# d150_zm1000_rev_a.net
KiCad netlist of a schematic drawn in EAGLE
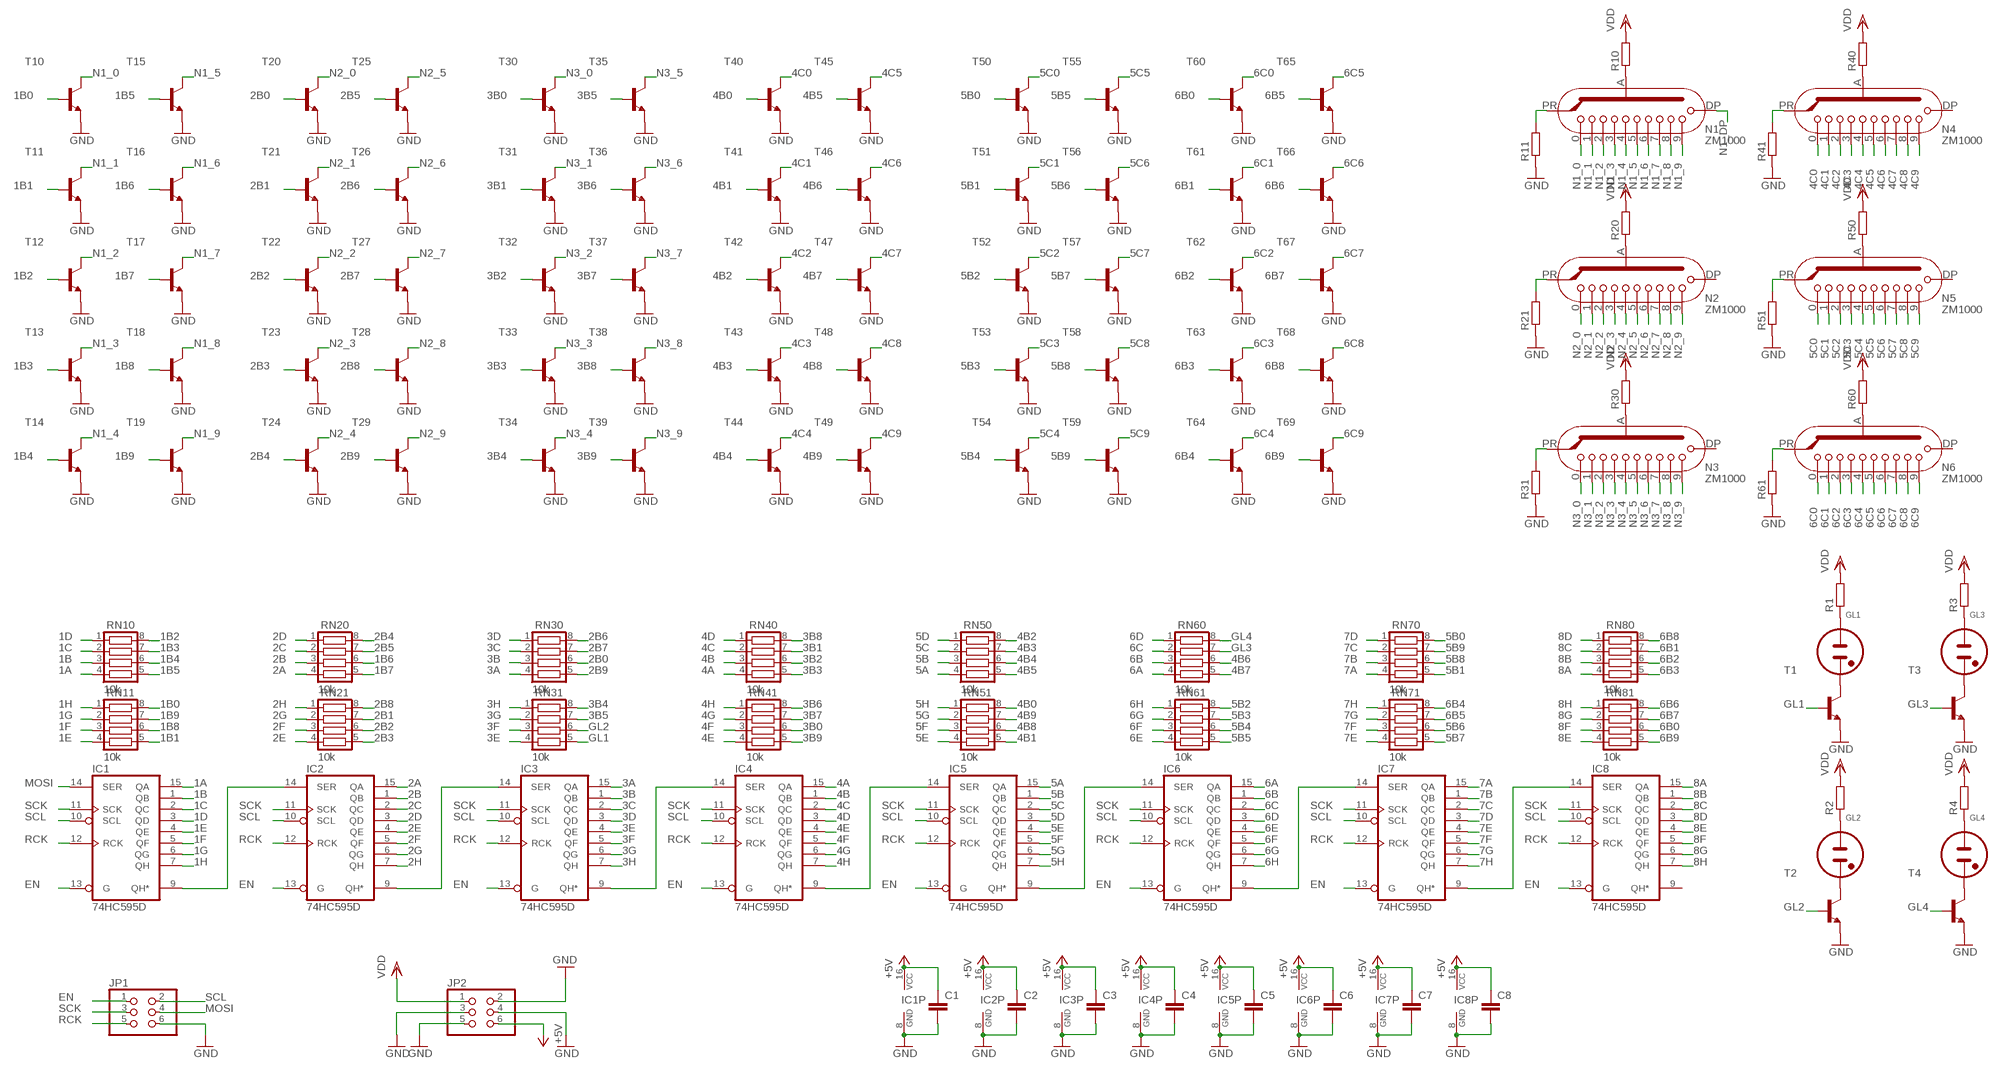
[diagram p0: schematic, sheet 1]

(export (version "E")
  (design (tool "Eeschema 10.0.6"))
  (components
    (comp (ref "C1")
      (value "C-EUC0603")
      (footprint "eagle-import:C0603")
      (libsource (lib "eagle-import") (part "C-EUC0603"))
    )
    (comp (ref "C2")
      (value "C-EUC0603")
      (footprint "eagle-import:C0603")
      (libsource (lib "eagle-import") (part "C-EUC0603"))
    )
    (comp (ref "C3")
      (value "C-EUC0603")
      (footprint "eagle-import:C0603")
      (libsource (lib "eagle-import") (part "C-EUC0603"))
    )
    (comp (ref "C4")
      (value "C-EUC0603")
      (footprint "eagle-import:C0603")
      (libsource (lib "eagle-import") (part "C-EUC0603"))
    )
    (comp (ref "C5")
      (value "C-EUC0603")
      (footprint "eagle-import:C0603")
      (libsource (lib "eagle-import") (part "C-EUC0603"))
    )
    (comp (ref "C6")
      (value "C-EUC0603")
      (footprint "eagle-import:C0603")
      (libsource (lib "eagle-import") (part "C-EUC0603"))
    )
    (comp (ref "C7")
      (value "C-EUC0603")
      (footprint "eagle-import:C0603")
      (libsource (lib "eagle-import") (part "C-EUC0603"))
    )
    (comp (ref "C8")
      (value "C-EUC0603")
      (footprint "eagle-import:C0603")
      (libsource (lib "eagle-import") (part "C-EUC0603"))
    )
    (comp (ref "GL1")
      (value "NE2-NEON-BULB-DRILL")
      (footprint "eagle-import:NE2-NEON-BULB-DRILL")
      (libsource (lib "eagle-import") (part "NE2-NEON-BULB-DRILL"))
    )
    (comp (ref "GL2")
      (value "NE2-NEON-BULB-DRILL")
      (footprint "eagle-import:NE2-NEON-BULB-DRILL")
      (libsource (lib "eagle-import") (part "NE2-NEON-BULB-DRILL"))
    )
    (comp (ref "GL3")
      (value "NE2-NEON-BULB-DRILL")
      (footprint "eagle-import:NE2-NEON-BULB-DRILL")
      (libsource (lib "eagle-import") (part "NE2-NEON-BULB-DRILL"))
    )
    (comp (ref "GL4")
      (value "NE2-NEON-BULB-DRILL")
      (footprint "eagle-import:NE2-NEON-BULB-DRILL")
      (libsource (lib "eagle-import") (part "NE2-NEON-BULB-DRILL"))
    )
    (comp (ref "IC1")
      (value "74HC595D")
      (footprint "eagle-import:SO16")
      (libsource (lib "eagle-import") (part "74595DHC"))
    )
    (comp (ref "IC2")
      (value "74HC595D")
      (footprint "eagle-import:SO16")
      (libsource (lib "eagle-import") (part "74595DHC"))
    )
    (comp (ref "IC3")
      (value "74HC595D")
      (footprint "eagle-import:SO16")
      (libsource (lib "eagle-import") (part "74595DHC"))
    )
    (comp (ref "IC4")
      (value "74HC595D")
      (footprint "eagle-import:SO16")
      (libsource (lib "eagle-import") (part "74595DHC"))
    )
    (comp (ref "IC5")
      (value "74HC595D")
      (footprint "eagle-import:SO16")
      (libsource (lib "eagle-import") (part "74595DHC"))
    )
    (comp (ref "IC6")
      (value "74HC595D")
      (footprint "eagle-import:SO16")
      (libsource (lib "eagle-import") (part "74595DHC"))
    )
    (comp (ref "IC7")
      (value "74HC595D")
      (footprint "eagle-import:SO16")
      (libsource (lib "eagle-import") (part "74595DHC"))
    )
    (comp (ref "IC8")
      (value "74HC595D")
      (footprint "eagle-import:SO16")
      (libsource (lib "eagle-import") (part "74595DHC"))
    )
    (comp (ref "JP1")
      (value "PINHD-2X3_2.54-SMD")
      (footprint "eagle-import:2X03SMD")
      (libsource (lib "eagle-import") (part "PINHD-2X3_2.54-SMD"))
    )
    (comp (ref "JP2")
      (value "PINHD-2X3_2.54-SMD")
      (footprint "eagle-import:2X03SMD")
      (libsource (lib "eagle-import") (part "PINHD-2X3_2.54-SMD"))
    )
    (comp (ref "N1")
      (value "ZM1000")
      (footprint "eagle-import:ZM1000")
      (libsource (lib "eagle-import") (part "ZM1000"))
    )
    (comp (ref "N2")
      (value "ZM1000")
      (footprint "eagle-import:ZM1000")
      (libsource (lib "eagle-import") (part "ZM1000"))
    )
    (comp (ref "N3")
      (value "ZM1000")
      (footprint "eagle-import:ZM1000")
      (libsource (lib "eagle-import") (part "ZM1000"))
    )
    (comp (ref "N4")
      (value "ZM1000")
      (footprint "eagle-import:ZM1000")
      (libsource (lib "eagle-import") (part "ZM1000"))
    )
    (comp (ref "N5")
      (value "ZM1000")
      (footprint "eagle-import:ZM1000")
      (libsource (lib "eagle-import") (part "ZM1000"))
    )
    (comp (ref "N6")
      (value "ZM1000")
      (footprint "eagle-import:ZM1000")
      (libsource (lib "eagle-import") (part "ZM1000"))
    )
    (comp (ref "R1")
      (value "R-EU_R0603")
      (footprint "eagle-import:R0603")
      (libsource (lib "eagle-import") (part "R-EU_R0603"))
    )
    (comp (ref "R2")
      (value "R-EU_R0603")
      (footprint "eagle-import:R0603")
      (libsource (lib "eagle-import") (part "R-EU_R0603"))
    )
    (comp (ref "R3")
      (value "R-EU_R0603")
      (footprint "eagle-import:R0603")
      (libsource (lib "eagle-import") (part "R-EU_R0603"))
    )
    (comp (ref "R4")
      (value "R-EU_R0603")
      (footprint "eagle-import:R0603")
      (libsource (lib "eagle-import") (part "R-EU_R0603"))
    )
    (comp (ref "R10")
      (value "R-EU_R0603")
      (footprint "eagle-import:R0603")
      (libsource (lib "eagle-import") (part "R-EU_R0603"))
    )
    (comp (ref "R11")
      (value "R-EU_R0603")
      (footprint "eagle-import:R0603")
      (libsource (lib "eagle-import") (part "R-EU_R0603"))
    )
    (comp (ref "R20")
      (value "R-EU_R0603")
      (footprint "eagle-import:R0603")
      (libsource (lib "eagle-import") (part "R-EU_R0603"))
    )
    (comp (ref "R21")
      (value "R-EU_R0603")
      (footprint "eagle-import:R0603")
      (libsource (lib "eagle-import") (part "R-EU_R0603"))
    )
    (comp (ref "R30")
      (value "R-EU_R0603")
      (footprint "eagle-import:R0603")
      (libsource (lib "eagle-import") (part "R-EU_R0603"))
    )
    (comp (ref "R31")
      (value "R-EU_R0603")
      (footprint "eagle-import:R0603")
      (libsource (lib "eagle-import") (part "R-EU_R0603"))
    )
    (comp (ref "R40")
      (value "R-EU_R0603")
      (footprint "eagle-import:R0603")
      (libsource (lib "eagle-import") (part "R-EU_R0603"))
    )
    (comp (ref "R41")
      (value "R-EU_R0603")
      (footprint "eagle-import:R0603")
      (libsource (lib "eagle-import") (part "R-EU_R0603"))
    )
    (comp (ref "R50")
      (value "R-EU_R0603")
      (footprint "eagle-import:R0603")
      (libsource (lib "eagle-import") (part "R-EU_R0603"))
    )
    (comp (ref "R51")
      (value "R-EU_R0603")
      (footprint "eagle-import:R0603")
      (libsource (lib "eagle-import") (part "R-EU_R0603"))
    )
    (comp (ref "R60")
      (value "R-EU_R0603")
      (footprint "eagle-import:R0603")
      (libsource (lib "eagle-import") (part "R-EU_R0603"))
    )
    (comp (ref "R61")
      (value "R-EU_R0603")
      (footprint "eagle-import:R0603")
      (libsource (lib "eagle-import") (part "R-EU_R0603"))
    )
    (comp (ref "RN10")
      (value "10k")
      (footprint "eagle-import:CTS742C083")
      (fields (field (name "OC_FARNELL") "unknown") (field (name "OC_NEWARK") "unknown"))
      (libsource (lib "eagle-import") (part "CTS742C083"))
    )
    (comp (ref "RN11")
      (value "10k")
      (footprint "eagle-import:CTS742C083")
      (fields (field (name "OC_FARNELL") "unknown") (field (name "OC_NEWARK") "unknown"))
      (libsource (lib "eagle-import") (part "CTS742C083"))
    )
    (comp (ref "RN20")
      (value "10k")
      (footprint "eagle-import:CTS742C083")
      (fields (field (name "OC_FARNELL") "unknown") (field (name "OC_NEWARK") "unknown"))
      (libsource (lib "eagle-import") (part "CTS742C083"))
    )
    (comp (ref "RN21")
      (value "10k")
      (footprint "eagle-import:CTS742C083")
      (fields (field (name "OC_FARNELL") "unknown") (field (name "OC_NEWARK") "unknown"))
      (libsource (lib "eagle-import") (part "CTS742C083"))
    )
    (comp (ref "RN30")
      (value "10k")
      (footprint "eagle-import:CTS742C083")
      (fields (field (name "OC_FARNELL") "unknown") (field (name "OC_NEWARK") "unknown"))
      (libsource (lib "eagle-import") (part "CTS742C083"))
    )
    (comp (ref "RN31")
      (value "10k")
      (footprint "eagle-import:CTS742C083")
      (fields (field (name "OC_FARNELL") "unknown") (field (name "OC_NEWARK") "unknown"))
      (libsource (lib "eagle-import") (part "CTS742C083"))
    )
    (comp (ref "RN40")
      (value "10k")
      (footprint "eagle-import:CTS742C083")
      (fields (field (name "OC_FARNELL") "unknown") (field (name "OC_NEWARK") "unknown"))
      (libsource (lib "eagle-import") (part "CTS742C083"))
    )
    (comp (ref "RN41")
      (value "10k")
      (footprint "eagle-import:CTS742C083")
      (fields (field (name "OC_FARNELL") "unknown") (field (name "OC_NEWARK") "unknown"))
      (libsource (lib "eagle-import") (part "CTS742C083"))
    )
    (comp (ref "RN50")
      (value "10k")
      (footprint "eagle-import:CTS742C083")
      (fields (field (name "OC_FARNELL") "unknown") (field (name "OC_NEWARK") "unknown"))
      (libsource (lib "eagle-import") (part "CTS742C083"))
    )
    (comp (ref "RN51")
      (value "10k")
      (footprint "eagle-import:CTS742C083")
      (fields (field (name "OC_FARNELL") "unknown") (field (name "OC_NEWARK") "unknown"))
      (libsource (lib "eagle-import") (part "CTS742C083"))
    )
    (comp (ref "RN60")
      (value "10k")
      (footprint "eagle-import:CTS742C083")
      (fields (field (name "OC_FARNELL") "unknown") (field (name "OC_NEWARK") "unknown"))
      (libsource (lib "eagle-import") (part "CTS742C083"))
    )
    (comp (ref "RN61")
      (value "10k")
      (footprint "eagle-import:CTS742C083")
      (fields (field (name "OC_FARNELL") "unknown") (field (name "OC_NEWARK") "unknown"))
      (libsource (lib "eagle-import") (part "CTS742C083"))
    )
    (comp (ref "RN70")
      (value "10k")
      (footprint "eagle-import:CTS742C083")
      (fields (field (name "OC_FARNELL") "unknown") (field (name "OC_NEWARK") "unknown"))
      (libsource (lib "eagle-import") (part "CTS742C083"))
    )
    (comp (ref "RN71")
      (value "10k")
      (footprint "eagle-import:CTS742C083")
      (fields (field (name "OC_FARNELL") "unknown") (field (name "OC_NEWARK") "unknown"))
      (libsource (lib "eagle-import") (part "CTS742C083"))
    )
    (comp (ref "RN80")
      (value "10k")
      (footprint "eagle-import:CTS742C083")
      (fields (field (name "OC_FARNELL") "unknown") (field (name "OC_NEWARK") "unknown"))
      (libsource (lib "eagle-import") (part "CTS742C083"))
    )
    (comp (ref "RN81")
      (value "10k")
      (footprint "eagle-import:CTS742C083")
      (fields (field (name "OC_FARNELL") "unknown") (field (name "OC_NEWARK") "unknown"))
      (libsource (lib "eagle-import") (part "CTS742C083"))
    )
    (comp (ref "T1")
      (value "SMBTA42")
      (footprint "eagle-import:SOT23")
      (libsource (lib "eagle-import") (part "SMBTA42"))
    )
    (comp (ref "T2")
      (value "SMBTA42")
      (footprint "eagle-import:SOT23")
      (libsource (lib "eagle-import") (part "SMBTA42"))
    )
    (comp (ref "T3")
      (value "SMBTA42")
      (footprint "eagle-import:SOT23")
      (libsource (lib "eagle-import") (part "SMBTA42"))
    )
    (comp (ref "T4")
      (value "SMBTA42")
      (footprint "eagle-import:SOT23")
      (libsource (lib "eagle-import") (part "SMBTA42"))
    )
    (comp (ref "T10")
      (value "SMBTA42")
      (footprint "eagle-import:SOT23")
      (libsource (lib "eagle-import") (part "SMBTA42"))
    )
    (comp (ref "T11")
      (value "SMBTA42")
      (footprint "eagle-import:SOT23")
      (libsource (lib "eagle-import") (part "SMBTA42"))
    )
    (comp (ref "T12")
      (value "SMBTA42")
      (footprint "eagle-import:SOT23")
      (libsource (lib "eagle-import") (part "SMBTA42"))
    )
    (comp (ref "T13")
      (value "SMBTA42")
      (footprint "eagle-import:SOT23")
      (libsource (lib "eagle-import") (part "SMBTA42"))
    )
    (comp (ref "T14")
      (value "SMBTA42")
      (footprint "eagle-import:SOT23")
      (libsource (lib "eagle-import") (part "SMBTA42"))
    )
    (comp (ref "T15")
      (value "SMBTA42")
      (footprint "eagle-import:SOT23")
      (libsource (lib "eagle-import") (part "SMBTA42"))
    )
    (comp (ref "T16")
      (value "SMBTA42")
      (footprint "eagle-import:SOT23")
      (libsource (lib "eagle-import") (part "SMBTA42"))
    )
    (comp (ref "T17")
      (value "SMBTA42")
      (footprint "eagle-import:SOT23")
      (libsource (lib "eagle-import") (part "SMBTA42"))
    )
    (comp (ref "T18")
      (value "SMBTA42")
      (footprint "eagle-import:SOT23")
      (libsource (lib "eagle-import") (part "SMBTA42"))
    )
    (comp (ref "T19")
      (value "SMBTA42")
      (footprint "eagle-import:SOT23")
      (libsource (lib "eagle-import") (part "SMBTA42"))
    )
    (comp (ref "T20")
      (value "SMBTA42")
      (footprint "eagle-import:SOT23")
      (libsource (lib "eagle-import") (part "SMBTA42"))
    )
    (comp (ref "T21")
      (value "SMBTA42")
      (footprint "eagle-import:SOT23")
      (libsource (lib "eagle-import") (part "SMBTA42"))
    )
    (comp (ref "T22")
      (value "SMBTA42")
      (footprint "eagle-import:SOT23")
      (libsource (lib "eagle-import") (part "SMBTA42"))
    )
    (comp (ref "T23")
      (value "SMBTA42")
      (footprint "eagle-import:SOT23")
      (libsource (lib "eagle-import") (part "SMBTA42"))
    )
    (comp (ref "T24")
      (value "SMBTA42")
      (footprint "eagle-import:SOT23")
      (libsource (lib "eagle-import") (part "SMBTA42"))
    )
    (comp (ref "T25")
      (value "SMBTA42")
      (footprint "eagle-import:SOT23")
      (libsource (lib "eagle-import") (part "SMBTA42"))
    )
    (comp (ref "T26")
      (value "SMBTA42")
      (footprint "eagle-import:SOT23")
      (libsource (lib "eagle-import") (part "SMBTA42"))
    )
    (comp (ref "T27")
      (value "SMBTA42")
      (footprint "eagle-import:SOT23")
      (libsource (lib "eagle-import") (part "SMBTA42"))
    )
    (comp (ref "T28")
      (value "SMBTA42")
      (footprint "eagle-import:SOT23")
      (libsource (lib "eagle-import") (part "SMBTA42"))
    )
    (comp (ref "T29")
      (value "SMBTA42")
      (footprint "eagle-import:SOT23")
      (libsource (lib "eagle-import") (part "SMBTA42"))
    )
    (comp (ref "T30")
      (value "SMBTA42")
      (footprint "eagle-import:SOT23")
      (libsource (lib "eagle-import") (part "SMBTA42"))
    )
    (comp (ref "T31")
      (value "SMBTA42")
      (footprint "eagle-import:SOT23")
      (libsource (lib "eagle-import") (part "SMBTA42"))
    )
    (comp (ref "T32")
      (value "SMBTA42")
      (footprint "eagle-import:SOT23")
      (libsource (lib "eagle-import") (part "SMBTA42"))
    )
    (comp (ref "T33")
      (value "SMBTA42")
      (footprint "eagle-import:SOT23")
      (libsource (lib "eagle-import") (part "SMBTA42"))
    )
    (comp (ref "T34")
      (value "SMBTA42")
      (footprint "eagle-import:SOT23")
      (libsource (lib "eagle-import") (part "SMBTA42"))
    )
    (comp (ref "T35")
      (value "SMBTA42")
      (footprint "eagle-import:SOT23")
      (libsource (lib "eagle-import") (part "SMBTA42"))
    )
    (comp (ref "T36")
      (value "SMBTA42")
      (footprint "eagle-import:SOT23")
      (libsource (lib "eagle-import") (part "SMBTA42"))
    )
    (comp (ref "T37")
      (value "SMBTA42")
      (footprint "eagle-import:SOT23")
      (libsource (lib "eagle-import") (part "SMBTA42"))
    )
    (comp (ref "T38")
      (value "SMBTA42")
      (footprint "eagle-import:SOT23")
      (libsource (lib "eagle-import") (part "SMBTA42"))
    )
    (comp (ref "T39")
      (value "SMBTA42")
      (footprint "eagle-import:SOT23")
      (libsource (lib "eagle-import") (part "SMBTA42"))
    )
    (comp (ref "T40")
      (value "SMBTA42")
      (footprint "eagle-import:SOT23")
      (libsource (lib "eagle-import") (part "SMBTA42"))
    )
    (comp (ref "T41")
      (value "SMBTA42")
      (footprint "eagle-import:SOT23")
      (libsource (lib "eagle-import") (part "SMBTA42"))
    )
    (comp (ref "T42")
      (value "SMBTA42")
      (footprint "eagle-import:SOT23")
      (libsource (lib "eagle-import") (part "SMBTA42"))
    )
    (comp (ref "T43")
      (value "SMBTA42")
      (footprint "eagle-import:SOT23")
      (libsource (lib "eagle-import") (part "SMBTA42"))
    )
    (comp (ref "T44")
      (value "SMBTA42")
      (footprint "eagle-import:SOT23")
      (libsource (lib "eagle-import") (part "SMBTA42"))
    )
    (comp (ref "T45")
      (value "SMBTA42")
      (footprint "eagle-import:SOT23")
      (libsource (lib "eagle-import") (part "SMBTA42"))
    )
    (comp (ref "T46")
      (value "SMBTA42")
      (footprint "eagle-import:SOT23")
      (libsource (lib "eagle-import") (part "SMBTA42"))
    )
    (comp (ref "T47")
      (value "SMBTA42")
      (footprint "eagle-import:SOT23")
      (libsource (lib "eagle-import") (part "SMBTA42"))
    )
    (comp (ref "T48")
      (value "SMBTA42")
      (footprint "eagle-import:SOT23")
      (libsource (lib "eagle-import") (part "SMBTA42"))
    )
    (comp (ref "T49")
      (value "SMBTA42")
      (footprint "eagle-import:SOT23")
      (libsource (lib "eagle-import") (part "SMBTA42"))
    )
    (comp (ref "T50")
      (value "SMBTA42")
      (footprint "eagle-import:SOT23")
      (libsource (lib "eagle-import") (part "SMBTA42"))
    )
    (comp (ref "T51")
      (value "SMBTA42")
      (footprint "eagle-import:SOT23")
      (libsource (lib "eagle-import") (part "SMBTA42"))
    )
    (comp (ref "T52")
      (value "SMBTA42")
      (footprint "eagle-import:SOT23")
      (libsource (lib "eagle-import") (part "SMBTA42"))
    )
    (comp (ref "T53")
      (value "SMBTA42")
      (footprint "eagle-import:SOT23")
      (libsource (lib "eagle-import") (part "SMBTA42"))
    )
    (comp (ref "T54")
      (value "SMBTA42")
      (footprint "eagle-import:SOT23")
      (libsource (lib "eagle-import") (part "SMBTA42"))
    )
    (comp (ref "T55")
      (value "SMBTA42")
      (footprint "eagle-import:SOT23")
      (libsource (lib "eagle-import") (part "SMBTA42"))
    )
    (comp (ref "T56")
      (value "SMBTA42")
      (footprint "eagle-import:SOT23")
      (libsource (lib "eagle-import") (part "SMBTA42"))
    )
    (comp (ref "T57")
      (value "SMBTA42")
      (footprint "eagle-import:SOT23")
      (libsource (lib "eagle-import") (part "SMBTA42"))
    )
    (comp (ref "T58")
      (value "SMBTA42")
      (footprint "eagle-import:SOT23")
      (libsource (lib "eagle-import") (part "SMBTA42"))
    )
    (comp (ref "T59")
      (value "SMBTA42")
      (footprint "eagle-import:SOT23")
      (libsource (lib "eagle-import") (part "SMBTA42"))
    )
    (comp (ref "T60")
      (value "SMBTA42")
      (footprint "eagle-import:SOT23")
      (libsource (lib "eagle-import") (part "SMBTA42"))
    )
    (comp (ref "T61")
      (value "SMBTA42")
      (footprint "eagle-import:SOT23")
      (libsource (lib "eagle-import") (part "SMBTA42"))
    )
    (comp (ref "T62")
      (value "SMBTA42")
      (footprint "eagle-import:SOT23")
      (libsource (lib "eagle-import") (part "SMBTA42"))
    )
    (comp (ref "T63")
      (value "SMBTA42")
      (footprint "eagle-import:SOT23")
      (libsource (lib "eagle-import") (part "SMBTA42"))
    )
    (comp (ref "T64")
      (value "SMBTA42")
      (footprint "eagle-import:SOT23")
      (libsource (lib "eagle-import") (part "SMBTA42"))
    )
    (comp (ref "T65")
      (value "SMBTA42")
      (footprint "eagle-import:SOT23")
      (libsource (lib "eagle-import") (part "SMBTA42"))
    )
    (comp (ref "T66")
      (value "SMBTA42")
      (footprint "eagle-import:SOT23")
      (libsource (lib "eagle-import") (part "SMBTA42"))
    )
    (comp (ref "T67")
      (value "SMBTA42")
      (footprint "eagle-import:SOT23")
      (libsource (lib "eagle-import") (part "SMBTA42"))
    )
    (comp (ref "T68")
      (value "SMBTA42")
      (footprint "eagle-import:SOT23")
      (libsource (lib "eagle-import") (part "SMBTA42"))
    )
    (comp (ref "T69")
      (value "SMBTA42")
      (footprint "eagle-import:SOT23")
      (libsource (lib "eagle-import") (part "SMBTA42"))
    )
  )
  (nets
    (net (code "1") (name "+5V") (class "Default")
      (node (ref "C1") (pin "1") (pinfunction "1_1") (pintype "passive"))
      (node (ref "C2") (pin "1") (pinfunction "1_1") (pintype "passive"))
      (node (ref "C3") (pin "1") (pinfunction "1_1") (pintype "passive"))
      (node (ref "C4") (pin "1") (pinfunction "1_1") (pintype "passive"))
      (node (ref "C5") (pin "1") (pinfunction "1_1") (pintype "passive"))
      (node (ref "C6") (pin "1") (pinfunction "1_1") (pintype "passive"))
      (node (ref "C7") (pin "1") (pinfunction "1_1") (pintype "passive"))
      (node (ref "C8") (pin "1") (pinfunction "1_1") (pintype "passive"))
      (node (ref "IC1") (pin "16") (pinfunction "VCC_16") (pintype "power_in"))
      (node (ref "IC2") (pin "16") (pinfunction "VCC_16") (pintype "power_in"))
      (node (ref "IC3") (pin "16") (pinfunction "VCC_16") (pintype "power_in"))
      (node (ref "IC4") (pin "16") (pinfunction "VCC_16") (pintype "power_in"))
      (node (ref "IC5") (pin "16") (pinfunction "VCC_16") (pintype "power_in"))
      (node (ref "IC6") (pin "16") (pinfunction "VCC_16") (pintype "power_in"))
      (node (ref "IC7") (pin "16") (pinfunction "VCC_16") (pintype "power_in"))
      (node (ref "IC8") (pin "16") (pinfunction "VCC_16") (pintype "power_in"))
      (node (ref "JP2") (pin "6") (pinfunction "6_6") (pintype "passive"))
    )
    (net (code "2") (name "/1A") (class "Default")
      (node (ref "IC1") (pin "15") (pinfunction "QA_15") (pintype "tri_state"))
      (node (ref "RN10") (pin "4") (pinfunction "4_4") (pintype "passive"))
    )
    (net (code "3") (name "/1B") (class "Default")
      (node (ref "IC1") (pin "1") (pinfunction "QB_1") (pintype "tri_state"))
      (node (ref "RN10") (pin "3") (pinfunction "3_3") (pintype "passive"))
    )
    (net (code "4") (name "/1B0") (class "Default")
      (node (ref "RN11") (pin "8") (pinfunction "8_8") (pintype "passive"))
      (node (ref "T10") (pin "1") (pinfunction "B_1") (pintype "passive"))
    )
    (net (code "5") (name "/1B1") (class "Default")
      (node (ref "RN11") (pin "5") (pinfunction "5_5") (pintype "passive"))
      (node (ref "T11") (pin "1") (pinfunction "B_1") (pintype "passive"))
    )
    (net (code "6") (name "/1B2") (class "Default")
      (node (ref "RN10") (pin "8") (pinfunction "8_8") (pintype "passive"))
      (node (ref "T12") (pin "1") (pinfunction "B_1") (pintype "passive"))
    )
    (net (code "7") (name "/1B3") (class "Default")
      (node (ref "RN10") (pin "7") (pinfunction "7_7") (pintype "passive"))
      (node (ref "T13") (pin "1") (pinfunction "B_1") (pintype "passive"))
    )
    (net (code "8") (name "/1B4") (class "Default")
      (node (ref "RN10") (pin "6") (pinfunction "6_6") (pintype "passive"))
      (node (ref "T14") (pin "1") (pinfunction "B_1") (pintype "passive"))
    )
    (net (code "9") (name "/1B5") (class "Default")
      (node (ref "RN10") (pin "5") (pinfunction "5_5") (pintype "passive"))
      (node (ref "T15") (pin "1") (pinfunction "B_1") (pintype "passive"))
    )
    (net (code "10") (name "/1B6") (class "Default")
      (node (ref "RN20") (pin "6") (pinfunction "6_6") (pintype "passive"))
      (node (ref "T16") (pin "1") (pinfunction "B_1") (pintype "passive"))
    )
    (net (code "11") (name "/1B7") (class "Default")
      (node (ref "RN20") (pin "5") (pinfunction "5_5") (pintype "passive"))
      (node (ref "T17") (pin "1") (pinfunction "B_1") (pintype "passive"))
    )
    (net (code "12") (name "/1B8") (class "Default")
      (node (ref "RN11") (pin "6") (pinfunction "6_6") (pintype "passive"))
      (node (ref "T18") (pin "1") (pinfunction "B_1") (pintype "passive"))
    )
    (net (code "13") (name "/1B9") (class "Default")
      (node (ref "RN11") (pin "7") (pinfunction "7_7") (pintype "passive"))
      (node (ref "T19") (pin "1") (pinfunction "B_1") (pintype "passive"))
    )
    (net (code "14") (name "/1C") (class "Default")
      (node (ref "IC1") (pin "2") (pinfunction "QC_2") (pintype "tri_state"))
      (node (ref "RN10") (pin "2") (pinfunction "2_2") (pintype "passive"))
    )
    (net (code "15") (name "/1D") (class "Default")
      (node (ref "IC1") (pin "3") (pinfunction "QD_3") (pintype "tri_state"))
      (node (ref "RN10") (pin "1") (pinfunction "1_1") (pintype "passive"))
    )
    (net (code "16") (name "/1E") (class "Default")
      (node (ref "IC1") (pin "4") (pinfunction "QE_4") (pintype "tri_state"))
      (node (ref "RN11") (pin "4") (pinfunction "4_4") (pintype "passive"))
    )
    (net (code "17") (name "/1F") (class "Default")
      (node (ref "IC1") (pin "5") (pinfunction "QF_5") (pintype "tri_state"))
      (node (ref "RN11") (pin "3") (pinfunction "3_3") (pintype "passive"))
    )
    (net (code "18") (name "/1G") (class "Default")
      (node (ref "IC1") (pin "6") (pinfunction "QG_6") (pintype "tri_state"))
      (node (ref "RN11") (pin "2") (pinfunction "2_2") (pintype "passive"))
    )
    (net (code "19") (name "/1H") (class "Default")
      (node (ref "IC1") (pin "7") (pinfunction "QH_7") (pintype "tri_state"))
      (node (ref "RN11") (pin "1") (pinfunction "1_1") (pintype "passive"))
    )
    (net (code "20") (name "/2A") (class "Default")
      (node (ref "IC2") (pin "15") (pinfunction "QA_15") (pintype "tri_state"))
      (node (ref "RN20") (pin "4") (pinfunction "4_4") (pintype "passive"))
    )
    (net (code "21") (name "/2B") (class "Default")
      (node (ref "IC2") (pin "1") (pinfunction "QB_1") (pintype "tri_state"))
      (node (ref "RN20") (pin "3") (pinfunction "3_3") (pintype "passive"))
    )
    (net (code "22") (name "/2B0") (class "Default")
      (node (ref "RN30") (pin "6") (pinfunction "6_6") (pintype "passive"))
      (node (ref "T20") (pin "1") (pinfunction "B_1") (pintype "passive"))
    )
    (net (code "23") (name "/2B1") (class "Default")
      (node (ref "RN21") (pin "7") (pinfunction "7_7") (pintype "passive"))
      (node (ref "T21") (pin "1") (pinfunction "B_1") (pintype "passive"))
    )
    (net (code "24") (name "/2B2") (class "Default")
      (node (ref "RN21") (pin "6") (pinfunction "6_6") (pintype "passive"))
      (node (ref "T22") (pin "1") (pinfunction "B_1") (pintype "passive"))
    )
    (net (code "25") (name "/2B3") (class "Default")
      (node (ref "RN21") (pin "5") (pinfunction "5_5") (pintype "passive"))
      (node (ref "T23") (pin "1") (pinfunction "B_1") (pintype "passive"))
    )
    (net (code "26") (name "/2B4") (class "Default")
      (node (ref "RN20") (pin "8") (pinfunction "8_8") (pintype "passive"))
      (node (ref "T24") (pin "1") (pinfunction "B_1") (pintype "passive"))
    )
    (net (code "27") (name "/2B5") (class "Default")
      (node (ref "RN20") (pin "7") (pinfunction "7_7") (pintype "passive"))
      (node (ref "T25") (pin "1") (pinfunction "B_1") (pintype "passive"))
    )
    (net (code "28") (name "/2B6") (class "Default")
      (node (ref "RN30") (pin "8") (pinfunction "8_8") (pintype "passive"))
      (node (ref "T26") (pin "1") (pinfunction "B_1") (pintype "passive"))
    )
    (net (code "29") (name "/2B7") (class "Default")
      (node (ref "RN30") (pin "7") (pinfunction "7_7") (pintype "passive"))
      (node (ref "T27") (pin "1") (pinfunction "B_1") (pintype "passive"))
    )
    (net (code "30") (name "/2B8") (class "Default")
      (node (ref "RN21") (pin "8") (pinfunction "8_8") (pintype "passive"))
      (node (ref "T28") (pin "1") (pinfunction "B_1") (pintype "passive"))
    )
    (net (code "31") (name "/2B9") (class "Default")
      (node (ref "RN30") (pin "5") (pinfunction "5_5") (pintype "passive"))
      (node (ref "T29") (pin "1") (pinfunction "B_1") (pintype "passive"))
    )
    (net (code "32") (name "/2C") (class "Default")
      (node (ref "IC2") (pin "2") (pinfunction "QC_2") (pintype "tri_state"))
      (node (ref "RN20") (pin "2") (pinfunction "2_2") (pintype "passive"))
    )
    (net (code "33") (name "/2D") (class "Default")
      (node (ref "IC2") (pin "3") (pinfunction "QD_3") (pintype "tri_state"))
      (node (ref "RN20") (pin "1") (pinfunction "1_1") (pintype "passive"))
    )
    (net (code "34") (name "/2E") (class "Default")
      (node (ref "IC2") (pin "4") (pinfunction "QE_4") (pintype "tri_state"))
      (node (ref "RN21") (pin "4") (pinfunction "4_4") (pintype "passive"))
    )
    (net (code "35") (name "/2F") (class "Default")
      (node (ref "IC2") (pin "5") (pinfunction "QF_5") (pintype "tri_state"))
      (node (ref "RN21") (pin "3") (pinfunction "3_3") (pintype "passive"))
    )
    (net (code "36") (name "/2G") (class "Default")
      (node (ref "IC2") (pin "6") (pinfunction "QG_6") (pintype "tri_state"))
      (node (ref "RN21") (pin "2") (pinfunction "2_2") (pintype "passive"))
    )
    (net (code "37") (name "/2H") (class "Default")
      (node (ref "IC2") (pin "7") (pinfunction "QH_7") (pintype "tri_state"))
      (node (ref "RN21") (pin "1") (pinfunction "1_1") (pintype "passive"))
    )
    (net (code "38") (name "/3A") (class "Default")
      (node (ref "IC3") (pin "15") (pinfunction "QA_15") (pintype "tri_state"))
      (node (ref "RN30") (pin "4") (pinfunction "4_4") (pintype "passive"))
    )
    (net (code "39") (name "/3B") (class "Default")
      (node (ref "IC3") (pin "1") (pinfunction "QB_1") (pintype "tri_state"))
      (node (ref "RN30") (pin "3") (pinfunction "3_3") (pintype "passive"))
    )
    (net (code "40") (name "/3B0") (class "Default")
      (node (ref "RN41") (pin "6") (pinfunction "6_6") (pintype "passive"))
      (node (ref "T30") (pin "1") (pinfunction "B_1") (pintype "passive"))
    )
    (net (code "41") (name "/3B1") (class "Default")
      (node (ref "RN40") (pin "7") (pinfunction "7_7") (pintype "passive"))
      (node (ref "T31") (pin "1") (pinfunction "B_1") (pintype "passive"))
    )
    (net (code "42") (name "/3B2") (class "Default")
      (node (ref "RN40") (pin "6") (pinfunction "6_6") (pintype "passive"))
      (node (ref "T32") (pin "1") (pinfunction "B_1") (pintype "passive"))
    )
    (net (code "43") (name "/3B3") (class "Default")
      (node (ref "RN40") (pin "5") (pinfunction "5_5") (pintype "passive"))
      (node (ref "T33") (pin "1") (pinfunction "B_1") (pintype "passive"))
    )
    (net (code "44") (name "/3B4") (class "Default")
      (node (ref "RN31") (pin "8") (pinfunction "8_8") (pintype "passive"))
      (node (ref "T34") (pin "1") (pinfunction "B_1") (pintype "passive"))
    )
    (net (code "45") (name "/3B5") (class "Default")
      (node (ref "RN31") (pin "7") (pinfunction "7_7") (pintype "passive"))
      (node (ref "T35") (pin "1") (pinfunction "B_1") (pintype "passive"))
    )
    (net (code "46") (name "/3B6") (class "Default")
      (node (ref "RN41") (pin "8") (pinfunction "8_8") (pintype "passive"))
      (node (ref "T36") (pin "1") (pinfunction "B_1") (pintype "passive"))
    )
    (net (code "47") (name "/3B7") (class "Default")
      (node (ref "RN41") (pin "7") (pinfunction "7_7") (pintype "passive"))
      (node (ref "T37") (pin "1") (pinfunction "B_1") (pintype "passive"))
    )
    (net (code "48") (name "/3B8") (class "Default")
      (node (ref "RN40") (pin "8") (pinfunction "8_8") (pintype "passive"))
      (node (ref "T38") (pin "1") (pinfunction "B_1") (pintype "passive"))
    )
    (net (code "49") (name "/3B9") (class "Default")
      (node (ref "RN41") (pin "5") (pinfunction "5_5") (pintype "passive"))
      (node (ref "T39") (pin "1") (pinfunction "B_1") (pintype "passive"))
    )
    (net (code "50") (name "/3C") (class "Default")
      (node (ref "IC3") (pin "2") (pinfunction "QC_2") (pintype "tri_state"))
      (node (ref "RN30") (pin "2") (pinfunction "2_2") (pintype "passive"))
    )
    (net (code "51") (name "/3D") (class "Default")
      (node (ref "IC3") (pin "3") (pinfunction "QD_3") (pintype "tri_state"))
      (node (ref "RN30") (pin "1") (pinfunction "1_1") (pintype "passive"))
    )
    (net (code "52") (name "/3E") (class "Default")
      (node (ref "IC3") (pin "4") (pinfunction "QE_4") (pintype "tri_state"))
      (node (ref "RN31") (pin "4") (pinfunction "4_4") (pintype "passive"))
    )
    (net (code "53") (name "/3F") (class "Default")
      (node (ref "IC3") (pin "5") (pinfunction "QF_5") (pintype "tri_state"))
      (node (ref "RN31") (pin "3") (pinfunction "3_3") (pintype "passive"))
    )
    (net (code "54") (name "/3G") (class "Default")
      (node (ref "IC3") (pin "6") (pinfunction "QG_6") (pintype "tri_state"))
      (node (ref "RN31") (pin "2") (pinfunction "2_2") (pintype "passive"))
    )
    (net (code "55") (name "/3H") (class "Default")
      (node (ref "IC3") (pin "7") (pinfunction "QH_7") (pintype "tri_state"))
      (node (ref "RN31") (pin "1") (pinfunction "1_1") (pintype "passive"))
    )
    (net (code "56") (name "/4A") (class "Default")
      (node (ref "IC4") (pin "15") (pinfunction "QA_15") (pintype "tri_state"))
      (node (ref "RN40") (pin "4") (pinfunction "4_4") (pintype "passive"))
    )
    (net (code "57") (name "/4B") (class "Default")
      (node (ref "IC4") (pin "1") (pinfunction "QB_1") (pintype "tri_state"))
      (node (ref "RN40") (pin "3") (pinfunction "3_3") (pintype "passive"))
    )
    (net (code "58") (name "/4B0") (class "Default")
      (node (ref "RN51") (pin "8") (pinfunction "8_8") (pintype "passive"))
      (node (ref "T40") (pin "1") (pinfunction "B_1") (pintype "passive"))
    )
    (net (code "59") (name "/4B1") (class "Default")
      (node (ref "RN51") (pin "5") (pinfunction "5_5") (pintype "passive"))
      (node (ref "T41") (pin "1") (pinfunction "B_1") (pintype "passive"))
    )
    (net (code "60") (name "/4B2") (class "Default")
      (node (ref "RN50") (pin "8") (pinfunction "8_8") (pintype "passive"))
      (node (ref "T42") (pin "1") (pinfunction "B_1") (pintype "passive"))
    )
    (net (code "61") (name "/4B3") (class "Default")
      (node (ref "RN50") (pin "7") (pinfunction "7_7") (pintype "passive"))
      (node (ref "T43") (pin "1") (pinfunction "B_1") (pintype "passive"))
    )
    (net (code "62") (name "/4B4") (class "Default")
      (node (ref "RN50") (pin "6") (pinfunction "6_6") (pintype "passive"))
      (node (ref "T44") (pin "1") (pinfunction "B_1") (pintype "passive"))
    )
    (net (code "63") (name "/4B5") (class "Default")
      (node (ref "RN50") (pin "5") (pinfunction "5_5") (pintype "passive"))
      (node (ref "T45") (pin "1") (pinfunction "B_1") (pintype "passive"))
    )
    (net (code "64") (name "/4B6") (class "Default")
      (node (ref "RN60") (pin "6") (pinfunction "6_6") (pintype "passive"))
      (node (ref "T46") (pin "1") (pinfunction "B_1") (pintype "passive"))
    )
    (net (code "65") (name "/4B7") (class "Default")
      (node (ref "RN60") (pin "5") (pinfunction "5_5") (pintype "passive"))
      (node (ref "T47") (pin "1") (pinfunction "B_1") (pintype "passive"))
    )
    (net (code "66") (name "/4B8") (class "Default")
      (node (ref "RN51") (pin "6") (pinfunction "6_6") (pintype "passive"))
      (node (ref "T48") (pin "1") (pinfunction "B_1") (pintype "passive"))
    )
    (net (code "67") (name "/4B9") (class "Default")
      (node (ref "RN51") (pin "7") (pinfunction "7_7") (pintype "passive"))
      (node (ref "T49") (pin "1") (pinfunction "B_1") (pintype "passive"))
    )
    (net (code "68") (name "/4C") (class "Default")
      (node (ref "IC4") (pin "2") (pinfunction "QC_2") (pintype "tri_state"))
      (node (ref "RN40") (pin "2") (pinfunction "2_2") (pintype "passive"))
    )
    (net (code "69") (name "/4C0") (class "Default")
      (node (ref "N4") (pin "K0") (pinfunction "0_K0") (pintype "bidirectional"))
      (node (ref "T40") (pin "3") (pinfunction "C_3") (pintype "passive"))
    )
    (net (code "70") (name "/4C1") (class "Default")
      (node (ref "N4") (pin "K1") (pinfunction "1_K1") (pintype "bidirectional"))
      (node (ref "T41") (pin "3") (pinfunction "C_3") (pintype "passive"))
    )
    (net (code "71") (name "/4C2") (class "Default")
      (node (ref "N4") (pin "K2") (pinfunction "2_K2") (pintype "bidirectional"))
      (node (ref "T42") (pin "3") (pinfunction "C_3") (pintype "passive"))
    )
    (net (code "72") (name "/4C3") (class "Default")
      (node (ref "N4") (pin "K3") (pinfunction "3_K3") (pintype "bidirectional"))
      (node (ref "T43") (pin "3") (pinfunction "C_3") (pintype "passive"))
    )
    (net (code "73") (name "/4C4") (class "Default")
      (node (ref "N4") (pin "K4") (pinfunction "4_K4") (pintype "bidirectional"))
      (node (ref "T44") (pin "3") (pinfunction "C_3") (pintype "passive"))
    )
    (net (code "74") (name "/4C5") (class "Default")
      (node (ref "N4") (pin "K5") (pinfunction "5_K5") (pintype "bidirectional"))
      (node (ref "T45") (pin "3") (pinfunction "C_3") (pintype "passive"))
    )
    (net (code "75") (name "/4C6") (class "Default")
      (node (ref "N4") (pin "K6") (pinfunction "6_K6") (pintype "bidirectional"))
      (node (ref "T46") (pin "3") (pinfunction "C_3") (pintype "passive"))
    )
    (net (code "76") (name "/4C7") (class "Default")
      (node (ref "N4") (pin "K7") (pinfunction "7_K7") (pintype "bidirectional"))
      (node (ref "T47") (pin "3") (pinfunction "C_3") (pintype "passive"))
    )
    (net (code "77") (name "/4C8") (class "Default")
      (node (ref "N4") (pin "K8") (pinfunction "8_K8") (pintype "bidirectional"))
      (node (ref "T48") (pin "3") (pinfunction "C_3") (pintype "passive"))
    )
    (net (code "78") (name "/4C9") (class "Default")
      (node (ref "N4") (pin "K9") (pinfunction "9_K9") (pintype "bidirectional"))
      (node (ref "T49") (pin "3") (pinfunction "C_3") (pintype "passive"))
    )
    (net (code "79") (name "/4D") (class "Default")
      (node (ref "IC4") (pin "3") (pinfunction "QD_3") (pintype "tri_state"))
      (node (ref "RN40") (pin "1") (pinfunction "1_1") (pintype "passive"))
    )
    (net (code "80") (name "/4E") (class "Default")
      (node (ref "IC4") (pin "4") (pinfunction "QE_4") (pintype "tri_state"))
      (node (ref "RN41") (pin "4") (pinfunction "4_4") (pintype "passive"))
    )
    (net (code "81") (name "/4F") (class "Default")
      (node (ref "IC4") (pin "5") (pinfunction "QF_5") (pintype "tri_state"))
      (node (ref "RN41") (pin "3") (pinfunction "3_3") (pintype "passive"))
    )
    (net (code "82") (name "/4G") (class "Default")
      (node (ref "IC4") (pin "6") (pinfunction "QG_6") (pintype "tri_state"))
      (node (ref "RN41") (pin "2") (pinfunction "2_2") (pintype "passive"))
    )
    (net (code "83") (name "/4H") (class "Default")
      (node (ref "IC4") (pin "7") (pinfunction "QH_7") (pintype "tri_state"))
      (node (ref "RN41") (pin "1") (pinfunction "1_1") (pintype "passive"))
    )
    (net (code "84") (name "/5A") (class "Default")
      (node (ref "IC5") (pin "15") (pinfunction "QA_15") (pintype "tri_state"))
      (node (ref "RN50") (pin "4") (pinfunction "4_4") (pintype "passive"))
    )
    (net (code "85") (name "/5B") (class "Default")
      (node (ref "IC5") (pin "1") (pinfunction "QB_1") (pintype "tri_state"))
      (node (ref "RN50") (pin "3") (pinfunction "3_3") (pintype "passive"))
    )
    (net (code "86") (name "/5B0") (class "Default")
      (node (ref "RN70") (pin "8") (pinfunction "8_8") (pintype "passive"))
      (node (ref "T50") (pin "1") (pinfunction "B_1") (pintype "passive"))
    )
    (net (code "87") (name "/5B1") (class "Default")
      (node (ref "RN70") (pin "5") (pinfunction "5_5") (pintype "passive"))
      (node (ref "T51") (pin "1") (pinfunction "B_1") (pintype "passive"))
    )
    (net (code "88") (name "/5B2") (class "Default")
      (node (ref "RN61") (pin "8") (pinfunction "8_8") (pintype "passive"))
      (node (ref "T52") (pin "1") (pinfunction "B_1") (pintype "passive"))
    )
    (net (code "89") (name "/5B3") (class "Default")
      (node (ref "RN61") (pin "7") (pinfunction "7_7") (pintype "passive"))
      (node (ref "T53") (pin "1") (pinfunction "B_1") (pintype "passive"))
    )
    (net (code "90") (name "/5B4") (class "Default")
      (node (ref "RN61") (pin "6") (pinfunction "6_6") (pintype "passive"))
      (node (ref "T54") (pin "1") (pinfunction "B_1") (pintype "passive"))
    )
    (net (code "91") (name "/5B5") (class "Default")
      (node (ref "RN61") (pin "5") (pinfunction "5_5") (pintype "passive"))
      (node (ref "T55") (pin "1") (pinfunction "B_1") (pintype "passive"))
    )
    (net (code "92") (name "/5B6") (class "Default")
      (node (ref "RN71") (pin "6") (pinfunction "6_6") (pintype "passive"))
      (node (ref "T56") (pin "1") (pinfunction "B_1") (pintype "passive"))
    )
    (net (code "93") (name "/5B7") (class "Default")
      (node (ref "RN71") (pin "5") (pinfunction "5_5") (pintype "passive"))
      (node (ref "T57") (pin "1") (pinfunction "B_1") (pintype "passive"))
    )
    (net (code "94") (name "/5B8") (class "Default")
      (node (ref "RN70") (pin "6") (pinfunction "6_6") (pintype "passive"))
      (node (ref "T58") (pin "1") (pinfunction "B_1") (pintype "passive"))
    )
    (net (code "95") (name "/5B9") (class "Default")
      (node (ref "RN70") (pin "7") (pinfunction "7_7") (pintype "passive"))
      (node (ref "T59") (pin "1") (pinfunction "B_1") (pintype "passive"))
    )
    (net (code "96") (name "/5C") (class "Default")
      (node (ref "IC5") (pin "2") (pinfunction "QC_2") (pintype "tri_state"))
      (node (ref "RN50") (pin "2") (pinfunction "2_2") (pintype "passive"))
    )
    (net (code "97") (name "/5C0") (class "Default")
      (node (ref "N5") (pin "K0") (pinfunction "0_K0") (pintype "bidirectional"))
      (node (ref "T50") (pin "3") (pinfunction "C_3") (pintype "passive"))
    )
    (net (code "98") (name "/5C1") (class "Default")
      (node (ref "N5") (pin "K1") (pinfunction "1_K1") (pintype "bidirectional"))
      (node (ref "T51") (pin "3") (pinfunction "C_3") (pintype "passive"))
    )
    (net (code "99") (name "/5C2") (class "Default")
      (node (ref "N5") (pin "K2") (pinfunction "2_K2") (pintype "bidirectional"))
      (node (ref "T52") (pin "3") (pinfunction "C_3") (pintype "passive"))
    )
    (net (code "100") (name "/5C3") (class "Default")
      (node (ref "N5") (pin "K3") (pinfunction "3_K3") (pintype "bidirectional"))
      (node (ref "T53") (pin "3") (pinfunction "C_3") (pintype "passive"))
    )
    (net (code "101") (name "/5C4") (class "Default")
      (node (ref "N5") (pin "K4") (pinfunction "4_K4") (pintype "bidirectional"))
      (node (ref "T54") (pin "3") (pinfunction "C_3") (pintype "passive"))
    )
    (net (code "102") (name "/5C5") (class "Default")
      (node (ref "N5") (pin "K5") (pinfunction "5_K5") (pintype "bidirectional"))
      (node (ref "T55") (pin "3") (pinfunction "C_3") (pintype "passive"))
    )
    (net (code "103") (name "/5C6") (class "Default")
      (node (ref "N5") (pin "K6") (pinfunction "6_K6") (pintype "bidirectional"))
      (node (ref "T56") (pin "3") (pinfunction "C_3") (pintype "passive"))
    )
    (net (code "104") (name "/5C7") (class "Default")
      (node (ref "N5") (pin "K7") (pinfunction "7_K7") (pintype "bidirectional"))
      (node (ref "T57") (pin "3") (pinfunction "C_3") (pintype "passive"))
    )
    (net (code "105") (name "/5C8") (class "Default")
      (node (ref "N5") (pin "K8") (pinfunction "8_K8") (pintype "bidirectional"))
      (node (ref "T58") (pin "3") (pinfunction "C_3") (pintype "passive"))
    )
    (net (code "106") (name "/5C9") (class "Default")
      (node (ref "N5") (pin "K9") (pinfunction "9_K9") (pintype "bidirectional"))
      (node (ref "T59") (pin "3") (pinfunction "C_3") (pintype "passive"))
    )
    (net (code "107") (name "/5D") (class "Default")
      (node (ref "IC5") (pin "3") (pinfunction "QD_3") (pintype "tri_state"))
      (node (ref "RN50") (pin "1") (pinfunction "1_1") (pintype "passive"))
    )
    (net (code "108") (name "/5E") (class "Default")
      (node (ref "IC5") (pin "4") (pinfunction "QE_4") (pintype "tri_state"))
      (node (ref "RN51") (pin "4") (pinfunction "4_4") (pintype "passive"))
    )
    (net (code "109") (name "/5F") (class "Default")
      (node (ref "IC5") (pin "5") (pinfunction "QF_5") (pintype "tri_state"))
      (node (ref "RN51") (pin "3") (pinfunction "3_3") (pintype "passive"))
    )
    (net (code "110") (name "/5G") (class "Default")
      (node (ref "IC5") (pin "6") (pinfunction "QG_6") (pintype "tri_state"))
      (node (ref "RN51") (pin "2") (pinfunction "2_2") (pintype "passive"))
    )
    (net (code "111") (name "/5H") (class "Default")
      (node (ref "IC5") (pin "7") (pinfunction "QH_7") (pintype "tri_state"))
      (node (ref "RN51") (pin "1") (pinfunction "1_1") (pintype "passive"))
    )
    (net (code "112") (name "/6A") (class "Default")
      (node (ref "IC6") (pin "15") (pinfunction "QA_15") (pintype "tri_state"))
      (node (ref "RN60") (pin "4") (pinfunction "4_4") (pintype "passive"))
    )
    (net (code "113") (name "/6B") (class "Default")
      (node (ref "IC6") (pin "1") (pinfunction "QB_1") (pintype "tri_state"))
      (node (ref "RN60") (pin "3") (pinfunction "3_3") (pintype "passive"))
    )
    (net (code "114") (name "/6B0") (class "Default")
      (node (ref "RN81") (pin "6") (pinfunction "6_6") (pintype "passive"))
      (node (ref "T60") (pin "1") (pinfunction "B_1") (pintype "passive"))
    )
    (net (code "115") (name "/6B1") (class "Default")
      (node (ref "RN80") (pin "7") (pinfunction "7_7") (pintype "passive"))
      (node (ref "T61") (pin "1") (pinfunction "B_1") (pintype "passive"))
    )
    (net (code "116") (name "/6B2") (class "Default")
      (node (ref "RN80") (pin "6") (pinfunction "6_6") (pintype "passive"))
      (node (ref "T62") (pin "1") (pinfunction "B_1") (pintype "passive"))
    )
    (net (code "117") (name "/6B3") (class "Default")
      (node (ref "RN80") (pin "5") (pinfunction "5_5") (pintype "passive"))
      (node (ref "T63") (pin "1") (pinfunction "B_1") (pintype "passive"))
    )
    (net (code "118") (name "/6B4") (class "Default")
      (node (ref "RN71") (pin "8") (pinfunction "8_8") (pintype "passive"))
      (node (ref "T64") (pin "1") (pinfunction "B_1") (pintype "passive"))
    )
    (net (code "119") (name "/6B5") (class "Default")
      (node (ref "RN71") (pin "7") (pinfunction "7_7") (pintype "passive"))
      (node (ref "T65") (pin "1") (pinfunction "B_1") (pintype "passive"))
    )
    (net (code "120") (name "/6B6") (class "Default")
      (node (ref "RN81") (pin "8") (pinfunction "8_8") (pintype "passive"))
      (node (ref "T66") (pin "1") (pinfunction "B_1") (pintype "passive"))
    )
    (net (code "121") (name "/6B7") (class "Default")
      (node (ref "RN81") (pin "7") (pinfunction "7_7") (pintype "passive"))
      (node (ref "T67") (pin "1") (pinfunction "B_1") (pintype "passive"))
    )
    (net (code "122") (name "/6B8") (class "Default")
      (node (ref "RN80") (pin "8") (pinfunction "8_8") (pintype "passive"))
      (node (ref "T68") (pin "1") (pinfunction "B_1") (pintype "passive"))
    )
    (net (code "123") (name "/6B9") (class "Default")
      (node (ref "RN81") (pin "5") (pinfunction "5_5") (pintype "passive"))
      (node (ref "T69") (pin "1") (pinfunction "B_1") (pintype "passive"))
    )
    (net (code "124") (name "/6C") (class "Default")
      (node (ref "IC6") (pin "2") (pinfunction "QC_2") (pintype "tri_state"))
      (node (ref "RN60") (pin "2") (pinfunction "2_2") (pintype "passive"))
    )
    (net (code "125") (name "/6C0") (class "Default")
      (node (ref "N6") (pin "K0") (pinfunction "0_K0") (pintype "bidirectional"))
      (node (ref "T60") (pin "3") (pinfunction "C_3") (pintype "passive"))
    )
    (net (code "126") (name "/6C1") (class "Default")
      (node (ref "N6") (pin "K1") (pinfunction "1_K1") (pintype "bidirectional"))
      (node (ref "T61") (pin "3") (pinfunction "C_3") (pintype "passive"))
    )
    (net (code "127") (name "/6C2") (class "Default")
      (node (ref "N6") (pin "K2") (pinfunction "2_K2") (pintype "bidirectional"))
      (node (ref "T62") (pin "3") (pinfunction "C_3") (pintype "passive"))
    )
    (net (code "128") (name "/6C3") (class "Default")
      (node (ref "N6") (pin "K3") (pinfunction "3_K3") (pintype "bidirectional"))
      (node (ref "T63") (pin "3") (pinfunction "C_3") (pintype "passive"))
    )
    (net (code "129") (name "/6C4") (class "Default")
      (node (ref "N6") (pin "K4") (pinfunction "4_K4") (pintype "bidirectional"))
      (node (ref "T64") (pin "3") (pinfunction "C_3") (pintype "passive"))
    )
    (net (code "130") (name "/6C5") (class "Default")
      (node (ref "N6") (pin "K5") (pinfunction "5_K5") (pintype "bidirectional"))
      (node (ref "T65") (pin "3") (pinfunction "C_3") (pintype "passive"))
    )
    (net (code "131") (name "/6C6") (class "Default")
      (node (ref "N6") (pin "K6") (pinfunction "6_K6") (pintype "bidirectional"))
      (node (ref "T66") (pin "3") (pinfunction "C_3") (pintype "passive"))
    )
    (net (code "132") (name "/6C7") (class "Default")
      (node (ref "N6") (pin "K7") (pinfunction "7_K7") (pintype "bidirectional"))
      (node (ref "T67") (pin "3") (pinfunction "C_3") (pintype "passive"))
    )
    (net (code "133") (name "/6C8") (class "Default")
      (node (ref "N6") (pin "K8") (pinfunction "8_K8") (pintype "bidirectional"))
      (node (ref "T68") (pin "3") (pinfunction "C_3") (pintype "passive"))
    )
    (net (code "134") (name "/6C9") (class "Default")
      (node (ref "N6") (pin "K9") (pinfunction "9_K9") (pintype "bidirectional"))
      (node (ref "T69") (pin "3") (pinfunction "C_3") (pintype "passive"))
    )
    (net (code "135") (name "/6D") (class "Default")
      (node (ref "IC6") (pin "3") (pinfunction "QD_3") (pintype "tri_state"))
      (node (ref "RN60") (pin "1") (pinfunction "1_1") (pintype "passive"))
    )
    (net (code "136") (name "/6E") (class "Default")
      (node (ref "IC6") (pin "4") (pinfunction "QE_4") (pintype "tri_state"))
      (node (ref "RN61") (pin "4") (pinfunction "4_4") (pintype "passive"))
    )
    (net (code "137") (name "/6F") (class "Default")
      (node (ref "IC6") (pin "5") (pinfunction "QF_5") (pintype "tri_state"))
      (node (ref "RN61") (pin "3") (pinfunction "3_3") (pintype "passive"))
    )
    (net (code "138") (name "/6G") (class "Default")
      (node (ref "IC6") (pin "6") (pinfunction "QG_6") (pintype "tri_state"))
      (node (ref "RN61") (pin "2") (pinfunction "2_2") (pintype "passive"))
    )
    (net (code "139") (name "/6H") (class "Default")
      (node (ref "IC6") (pin "7") (pinfunction "QH_7") (pintype "tri_state"))
      (node (ref "RN61") (pin "1") (pinfunction "1_1") (pintype "passive"))
    )
    (net (code "140") (name "/7A") (class "Default")
      (node (ref "IC7") (pin "15") (pinfunction "QA_15") (pintype "tri_state"))
      (node (ref "RN70") (pin "4") (pinfunction "4_4") (pintype "passive"))
    )
    (net (code "141") (name "/7B") (class "Default")
      (node (ref "IC7") (pin "1") (pinfunction "QB_1") (pintype "tri_state"))
      (node (ref "RN70") (pin "3") (pinfunction "3_3") (pintype "passive"))
    )
    (net (code "142") (name "/7C") (class "Default")
      (node (ref "IC7") (pin "2") (pinfunction "QC_2") (pintype "tri_state"))
      (node (ref "RN70") (pin "2") (pinfunction "2_2") (pintype "passive"))
    )
    (net (code "143") (name "/7D") (class "Default")
      (node (ref "IC7") (pin "3") (pinfunction "QD_3") (pintype "tri_state"))
      (node (ref "RN70") (pin "1") (pinfunction "1_1") (pintype "passive"))
    )
    (net (code "144") (name "/7E") (class "Default")
      (node (ref "IC7") (pin "4") (pinfunction "QE_4") (pintype "tri_state"))
      (node (ref "RN71") (pin "4") (pinfunction "4_4") (pintype "passive"))
    )
    (net (code "145") (name "/7F") (class "Default")
      (node (ref "IC7") (pin "5") (pinfunction "QF_5") (pintype "tri_state"))
      (node (ref "RN71") (pin "3") (pinfunction "3_3") (pintype "passive"))
    )
    (net (code "146") (name "/7G") (class "Default")
      (node (ref "IC7") (pin "6") (pinfunction "QG_6") (pintype "tri_state"))
      (node (ref "RN71") (pin "2") (pinfunction "2_2") (pintype "passive"))
    )
    (net (code "147") (name "/7H") (class "Default")
      (node (ref "IC7") (pin "7") (pinfunction "QH_7") (pintype "tri_state"))
      (node (ref "RN71") (pin "1") (pinfunction "1_1") (pintype "passive"))
    )
    (net (code "148") (name "/8A") (class "Default")
      (node (ref "IC8") (pin "15") (pinfunction "QA_15") (pintype "tri_state"))
      (node (ref "RN80") (pin "4") (pinfunction "4_4") (pintype "passive"))
    )
    (net (code "149") (name "/8B") (class "Default")
      (node (ref "IC8") (pin "1") (pinfunction "QB_1") (pintype "tri_state"))
      (node (ref "RN80") (pin "3") (pinfunction "3_3") (pintype "passive"))
    )
    (net (code "150") (name "/8C") (class "Default")
      (node (ref "IC8") (pin "2") (pinfunction "QC_2") (pintype "tri_state"))
      (node (ref "RN80") (pin "2") (pinfunction "2_2") (pintype "passive"))
    )
    (net (code "151") (name "/8D") (class "Default")
      (node (ref "IC8") (pin "3") (pinfunction "QD_3") (pintype "tri_state"))
      (node (ref "RN80") (pin "1") (pinfunction "1_1") (pintype "passive"))
    )
    (net (code "152") (name "/8E") (class "Default")
      (node (ref "IC8") (pin "4") (pinfunction "QE_4") (pintype "tri_state"))
      (node (ref "RN81") (pin "4") (pinfunction "4_4") (pintype "passive"))
    )
    (net (code "153") (name "/8F") (class "Default")
      (node (ref "IC8") (pin "5") (pinfunction "QF_5") (pintype "tri_state"))
      (node (ref "RN81") (pin "3") (pinfunction "3_3") (pintype "passive"))
    )
    (net (code "154") (name "/8G") (class "Default")
      (node (ref "IC8") (pin "6") (pinfunction "QG_6") (pintype "tri_state"))
      (node (ref "RN81") (pin "2") (pinfunction "2_2") (pintype "passive"))
    )
    (net (code "155") (name "/8H") (class "Default")
      (node (ref "IC8") (pin "7") (pinfunction "QH_7") (pintype "tri_state"))
      (node (ref "RN81") (pin "1") (pinfunction "1_1") (pintype "passive"))
    )
    (net (code "156") (name "/EN") (class "Default")
      (node (ref "IC1") (pin "13") (pinfunction "G_13") (pintype "input"))
      (node (ref "IC2") (pin "13") (pinfunction "G_13") (pintype "input"))
      (node (ref "IC3") (pin "13") (pinfunction "G_13") (pintype "input"))
      (node (ref "IC4") (pin "13") (pinfunction "G_13") (pintype "input"))
      (node (ref "IC5") (pin "13") (pinfunction "G_13") (pintype "input"))
      (node (ref "IC6") (pin "13") (pinfunction "G_13") (pintype "input"))
      (node (ref "IC7") (pin "13") (pinfunction "G_13") (pintype "input"))
      (node (ref "IC8") (pin "13") (pinfunction "G_13") (pintype "input"))
      (node (ref "JP1") (pin "1") (pinfunction "1_1") (pintype "passive"))
    )
    (net (code "157") (name "/GL1") (class "Default")
      (node (ref "RN31") (pin "5") (pinfunction "5_5") (pintype "passive"))
      (node (ref "T1") (pin "1") (pinfunction "B_1") (pintype "passive"))
    )
    (net (code "158") (name "/GL2") (class "Default")
      (node (ref "RN31") (pin "6") (pinfunction "6_6") (pintype "passive"))
      (node (ref "T2") (pin "1") (pinfunction "B_1") (pintype "passive"))
    )
    (net (code "159") (name "/GL3") (class "Default")
      (node (ref "RN60") (pin "7") (pinfunction "7_7") (pintype "passive"))
      (node (ref "T3") (pin "1") (pinfunction "B_1") (pintype "passive"))
    )
    (net (code "160") (name "/GL4") (class "Default")
      (node (ref "RN60") (pin "8") (pinfunction "8_8") (pintype "passive"))
      (node (ref "T4") (pin "1") (pinfunction "B_1") (pintype "passive"))
    )
    (net (code "161") (name "/MOSI") (class "Default")
      (node (ref "IC1") (pin "14") (pinfunction "SER_14") (pintype "input"))
      (node (ref "JP1") (pin "4") (pinfunction "4_4") (pintype "passive"))
    )
    (net (code "162") (name "/N1_0") (class "Default")
      (node (ref "N1") (pin "K0") (pinfunction "0_K0") (pintype "bidirectional"))
      (node (ref "T10") (pin "3") (pinfunction "C_3") (pintype "passive"))
    )
    (net (code "163") (name "/N1_1") (class "Default")
      (node (ref "N1") (pin "K1") (pinfunction "1_K1") (pintype "bidirectional"))
      (node (ref "T11") (pin "3") (pinfunction "C_3") (pintype "passive"))
    )
    (net (code "164") (name "/N1_2") (class "Default")
      (node (ref "N1") (pin "K2") (pinfunction "2_K2") (pintype "bidirectional"))
      (node (ref "T12") (pin "3") (pinfunction "C_3") (pintype "passive"))
    )
    (net (code "165") (name "/N1_3") (class "Default")
      (node (ref "N1") (pin "K3") (pinfunction "3_K3") (pintype "bidirectional"))
      (node (ref "T13") (pin "3") (pinfunction "C_3") (pintype "passive"))
    )
    (net (code "166") (name "/N1_4") (class "Default")
      (node (ref "N1") (pin "K4") (pinfunction "4_K4") (pintype "bidirectional"))
      (node (ref "T14") (pin "3") (pinfunction "C_3") (pintype "passive"))
    )
    (net (code "167") (name "/N1_5") (class "Default")
      (node (ref "N1") (pin "K5") (pinfunction "5_K5") (pintype "bidirectional"))
      (node (ref "T15") (pin "3") (pinfunction "C_3") (pintype "passive"))
    )
    (net (code "168") (name "/N1_6") (class "Default")
      (node (ref "N1") (pin "K6") (pinfunction "6_K6") (pintype "bidirectional"))
      (node (ref "T16") (pin "3") (pinfunction "C_3") (pintype "passive"))
    )
    (net (code "169") (name "/N1_7") (class "Default")
      (node (ref "N1") (pin "K7") (pinfunction "7_K7") (pintype "bidirectional"))
      (node (ref "T17") (pin "3") (pinfunction "C_3") (pintype "passive"))
    )
    (net (code "170") (name "/N1_8") (class "Default")
      (node (ref "N1") (pin "K8") (pinfunction "8_K8") (pintype "bidirectional"))
      (node (ref "T18") (pin "3") (pinfunction "C_3") (pintype "passive"))
    )
    (net (code "171") (name "/N1_9") (class "Default")
      (node (ref "N1") (pin "K9") (pinfunction "9_K9") (pintype "bidirectional"))
      (node (ref "T19") (pin "3") (pinfunction "C_3") (pintype "passive"))
    )
    (net (code "172") (name "/N1_DP") (class "Default")
      (node (ref "N1") (pin "KDP") (pinfunction "DP_KDP") (pintype "bidirectional"))
    )
    (net (code "173") (name "/N2_0") (class "Default")
      (node (ref "N2") (pin "K0") (pinfunction "0_K0") (pintype "bidirectional"))
      (node (ref "T20") (pin "3") (pinfunction "C_3") (pintype "passive"))
    )
    (net (code "174") (name "/N2_1") (class "Default")
      (node (ref "N2") (pin "K1") (pinfunction "1_K1") (pintype "bidirectional"))
      (node (ref "T21") (pin "3") (pinfunction "C_3") (pintype "passive"))
    )
    (net (code "175") (name "/N2_2") (class "Default")
      (node (ref "N2") (pin "K2") (pinfunction "2_K2") (pintype "bidirectional"))
      (node (ref "T22") (pin "3") (pinfunction "C_3") (pintype "passive"))
    )
    (net (code "176") (name "/N2_3") (class "Default")
      (node (ref "N2") (pin "K3") (pinfunction "3_K3") (pintype "bidirectional"))
      (node (ref "T23") (pin "3") (pinfunction "C_3") (pintype "passive"))
    )
    (net (code "177") (name "/N2_4") (class "Default")
      (node (ref "N2") (pin "K4") (pinfunction "4_K4") (pintype "bidirectional"))
      (node (ref "T24") (pin "3") (pinfunction "C_3") (pintype "passive"))
    )
    (net (code "178") (name "/N2_5") (class "Default")
      (node (ref "N2") (pin "K5") (pinfunction "5_K5") (pintype "bidirectional"))
      (node (ref "T25") (pin "3") (pinfunction "C_3") (pintype "passive"))
    )
    (net (code "179") (name "/N2_6") (class "Default")
      (node (ref "N2") (pin "K6") (pinfunction "6_K6") (pintype "bidirectional"))
      (node (ref "T26") (pin "3") (pinfunction "C_3") (pintype "passive"))
    )
    (net (code "180") (name "/N2_7") (class "Default")
      (node (ref "N2") (pin "K7") (pinfunction "7_K7") (pintype "bidirectional"))
      (node (ref "T27") (pin "3") (pinfunction "C_3") (pintype "passive"))
    )
    (net (code "181") (name "/N2_8") (class "Default")
      (node (ref "N2") (pin "K8") (pinfunction "8_K8") (pintype "bidirectional"))
      (node (ref "T28") (pin "3") (pinfunction "C_3") (pintype "passive"))
    )
    (net (code "182") (name "/N2_9") (class "Default")
      (node (ref "N2") (pin "K9") (pinfunction "9_K9") (pintype "bidirectional"))
      (node (ref "T29") (pin "3") (pinfunction "C_3") (pintype "passive"))
    )
    (net (code "183") (name "/N3_0") (class "Default")
      (node (ref "N3") (pin "K0") (pinfunction "0_K0") (pintype "bidirectional"))
      (node (ref "T30") (pin "3") (pinfunction "C_3") (pintype "passive"))
    )
    (net (code "184") (name "/N3_1") (class "Default")
      (node (ref "N3") (pin "K1") (pinfunction "1_K1") (pintype "bidirectional"))
      (node (ref "T31") (pin "3") (pinfunction "C_3") (pintype "passive"))
    )
    (net (code "185") (name "/N3_2") (class "Default")
      (node (ref "N3") (pin "K2") (pinfunction "2_K2") (pintype "bidirectional"))
      (node (ref "T32") (pin "3") (pinfunction "C_3") (pintype "passive"))
    )
    (net (code "186") (name "/N3_3") (class "Default")
      (node (ref "N3") (pin "K3") (pinfunction "3_K3") (pintype "bidirectional"))
      (node (ref "T33") (pin "3") (pinfunction "C_3") (pintype "passive"))
    )
    (net (code "187") (name "/N3_4") (class "Default")
      (node (ref "N3") (pin "K4") (pinfunction "4_K4") (pintype "bidirectional"))
      (node (ref "T34") (pin "3") (pinfunction "C_3") (pintype "passive"))
    )
    (net (code "188") (name "/N3_5") (class "Default")
      (node (ref "N3") (pin "K5") (pinfunction "5_K5") (pintype "bidirectional"))
      (node (ref "T35") (pin "3") (pinfunction "C_3") (pintype "passive"))
    )
    (net (code "189") (name "/N3_6") (class "Default")
      (node (ref "N3") (pin "K6") (pinfunction "6_K6") (pintype "bidirectional"))
      (node (ref "T36") (pin "3") (pinfunction "C_3") (pintype "passive"))
    )
    (net (code "190") (name "/N3_7") (class "Default")
      (node (ref "N3") (pin "K7") (pinfunction "7_K7") (pintype "bidirectional"))
      (node (ref "T37") (pin "3") (pinfunction "C_3") (pintype "passive"))
    )
    (net (code "191") (name "/N3_8") (class "Default")
      (node (ref "N3") (pin "K8") (pinfunction "8_K8") (pintype "bidirectional"))
      (node (ref "T38") (pin "3") (pinfunction "C_3") (pintype "passive"))
    )
    (net (code "192") (name "/N3_9") (class "Default")
      (node (ref "N3") (pin "K9") (pinfunction "9_K9") (pintype "bidirectional"))
      (node (ref "T39") (pin "3") (pinfunction "C_3") (pintype "passive"))
    )
    (net (code "193") (name "/RCK") (class "Default")
      (node (ref "IC1") (pin "12") (pinfunction "RCK_12") (pintype "input"))
      (node (ref "IC2") (pin "12") (pinfunction "RCK_12") (pintype "input"))
      (node (ref "IC3") (pin "12") (pinfunction "RCK_12") (pintype "input"))
      (node (ref "IC4") (pin "12") (pinfunction "RCK_12") (pintype "input"))
      (node (ref "IC5") (pin "12") (pinfunction "RCK_12") (pintype "input"))
      (node (ref "IC6") (pin "12") (pinfunction "RCK_12") (pintype "input"))
      (node (ref "IC7") (pin "12") (pinfunction "RCK_12") (pintype "input"))
      (node (ref "IC8") (pin "12") (pinfunction "RCK_12") (pintype "input"))
      (node (ref "JP1") (pin "5") (pinfunction "5_5") (pintype "passive"))
    )
    (net (code "194") (name "/SCK") (class "Default")
      (node (ref "IC1") (pin "11") (pinfunction "SCK_11") (pintype "input"))
      (node (ref "IC2") (pin "11") (pinfunction "SCK_11") (pintype "input"))
      (node (ref "IC3") (pin "11") (pinfunction "SCK_11") (pintype "input"))
      (node (ref "IC4") (pin "11") (pinfunction "SCK_11") (pintype "input"))
      (node (ref "IC5") (pin "11") (pinfunction "SCK_11") (pintype "input"))
      (node (ref "IC6") (pin "11") (pinfunction "SCK_11") (pintype "input"))
      (node (ref "IC7") (pin "11") (pinfunction "SCK_11") (pintype "input"))
      (node (ref "IC8") (pin "11") (pinfunction "SCK_11") (pintype "input"))
      (node (ref "JP1") (pin "3") (pinfunction "3_3") (pintype "passive"))
    )
    (net (code "195") (name "/SCL") (class "Default")
      (node (ref "IC1") (pin "10") (pinfunction "SCL_10") (pintype "input"))
      (node (ref "IC2") (pin "10") (pinfunction "SCL_10") (pintype "input"))
      (node (ref "IC3") (pin "10") (pinfunction "SCL_10") (pintype "input"))
      (node (ref "IC4") (pin "10") (pinfunction "SCL_10") (pintype "input"))
      (node (ref "IC5") (pin "10") (pinfunction "SCL_10") (pintype "input"))
      (node (ref "IC6") (pin "10") (pinfunction "SCL_10") (pintype "input"))
      (node (ref "IC7") (pin "10") (pinfunction "SCL_10") (pintype "input"))
      (node (ref "IC8") (pin "10") (pinfunction "SCL_10") (pintype "input"))
      (node (ref "JP1") (pin "2") (pinfunction "2_2") (pintype "passive"))
    )
    (net (code "196") (name "GND") (class "Default")
      (node (ref "C1") (pin "2") (pinfunction "2_2") (pintype "passive"))
      (node (ref "C2") (pin "2") (pinfunction "2_2") (pintype "passive"))
      (node (ref "C3") (pin "2") (pinfunction "2_2") (pintype "passive"))
      (node (ref "C4") (pin "2") (pinfunction "2_2") (pintype "passive"))
      (node (ref "C5") (pin "2") (pinfunction "2_2") (pintype "passive"))
      (node (ref "C6") (pin "2") (pinfunction "2_2") (pintype "passive"))
      (node (ref "C7") (pin "2") (pinfunction "2_2") (pintype "passive"))
      (node (ref "C8") (pin "2") (pinfunction "2_2") (pintype "passive"))
      (node (ref "IC1") (pin "8") (pinfunction "GND_8") (pintype "power_in"))
      (node (ref "IC2") (pin "8") (pinfunction "GND_8") (pintype "power_in"))
      (node (ref "IC3") (pin "8") (pinfunction "GND_8") (pintype "power_in"))
      (node (ref "IC4") (pin "8") (pinfunction "GND_8") (pintype "power_in"))
      (node (ref "IC5") (pin "8") (pinfunction "GND_8") (pintype "power_in"))
      (node (ref "IC6") (pin "8") (pinfunction "GND_8") (pintype "power_in"))
      (node (ref "IC7") (pin "8") (pinfunction "GND_8") (pintype "power_in"))
      (node (ref "IC8") (pin "8") (pinfunction "GND_8") (pintype "power_in"))
      (node (ref "JP1") (pin "6") (pinfunction "6_6") (pintype "passive"))
      (node (ref "JP2") (pin "2") (pinfunction "2_2") (pintype "passive"))
      (node (ref "JP2") (pin "3") (pinfunction "3_3") (pintype "passive"))
      (node (ref "JP2") (pin "4") (pinfunction "4_4") (pintype "passive"))
      (node (ref "JP2") (pin "5") (pinfunction "5_5") (pintype "passive"))
      (node (ref "R11") (pin "1") (pinfunction "1_1") (pintype "passive"))
      (node (ref "R21") (pin "1") (pinfunction "1_1") (pintype "passive"))
      (node (ref "R31") (pin "1") (pinfunction "1_1") (pintype "passive"))
      (node (ref "R41") (pin "1") (pinfunction "1_1") (pintype "passive"))
      (node (ref "R51") (pin "1") (pinfunction "1_1") (pintype "passive"))
      (node (ref "R61") (pin "1") (pinfunction "1_1") (pintype "passive"))
      (node (ref "T1") (pin "2") (pinfunction "E_2") (pintype "passive"))
      (node (ref "T10") (pin "2") (pinfunction "E_2") (pintype "passive"))
      (node (ref "T11") (pin "2") (pinfunction "E_2") (pintype "passive"))
      (node (ref "T12") (pin "2") (pinfunction "E_2") (pintype "passive"))
      (node (ref "T13") (pin "2") (pinfunction "E_2") (pintype "passive"))
      (node (ref "T14") (pin "2") (pinfunction "E_2") (pintype "passive"))
      (node (ref "T15") (pin "2") (pinfunction "E_2") (pintype "passive"))
      (node (ref "T16") (pin "2") (pinfunction "E_2") (pintype "passive"))
      (node (ref "T17") (pin "2") (pinfunction "E_2") (pintype "passive"))
      (node (ref "T18") (pin "2") (pinfunction "E_2") (pintype "passive"))
      (node (ref "T19") (pin "2") (pinfunction "E_2") (pintype "passive"))
      (node (ref "T2") (pin "2") (pinfunction "E_2") (pintype "passive"))
      (node (ref "T20") (pin "2") (pinfunction "E_2") (pintype "passive"))
      (node (ref "T21") (pin "2") (pinfunction "E_2") (pintype "passive"))
      (node (ref "T22") (pin "2") (pinfunction "E_2") (pintype "passive"))
      (node (ref "T23") (pin "2") (pinfunction "E_2") (pintype "passive"))
      (node (ref "T24") (pin "2") (pinfunction "E_2") (pintype "passive"))
      (node (ref "T25") (pin "2") (pinfunction "E_2") (pintype "passive"))
      (node (ref "T26") (pin "2") (pinfunction "E_2") (pintype "passive"))
      (node (ref "T27") (pin "2") (pinfunction "E_2") (pintype "passive"))
      (node (ref "T28") (pin "2") (pinfunction "E_2") (pintype "passive"))
      (node (ref "T29") (pin "2") (pinfunction "E_2") (pintype "passive"))
      (node (ref "T3") (pin "2") (pinfunction "E_2") (pintype "passive"))
      (node (ref "T30") (pin "2") (pinfunction "E_2") (pintype "passive"))
      (node (ref "T31") (pin "2") (pinfunction "E_2") (pintype "passive"))
      (node (ref "T32") (pin "2") (pinfunction "E_2") (pintype "passive"))
      (node (ref "T33") (pin "2") (pinfunction "E_2") (pintype "passive"))
      (node (ref "T34") (pin "2") (pinfunction "E_2") (pintype "passive"))
      (node (ref "T35") (pin "2") (pinfunction "E_2") (pintype "passive"))
      (node (ref "T36") (pin "2") (pinfunction "E_2") (pintype "passive"))
      (node (ref "T37") (pin "2") (pinfunction "E_2") (pintype "passive"))
      (node (ref "T38") (pin "2") (pinfunction "E_2") (pintype "passive"))
      (node (ref "T39") (pin "2") (pinfunction "E_2") (pintype "passive"))
      (node (ref "T4") (pin "2") (pinfunction "E_2") (pintype "passive"))
      (node (ref "T40") (pin "2") (pinfunction "E_2") (pintype "passive"))
      (node (ref "T41") (pin "2") (pinfunction "E_2") (pintype "passive"))
      (node (ref "T42") (pin "2") (pinfunction "E_2") (pintype "passive"))
      (node (ref "T43") (pin "2") (pinfunction "E_2") (pintype "passive"))
      (node (ref "T44") (pin "2") (pinfunction "E_2") (pintype "passive"))
      (node (ref "T45") (pin "2") (pinfunction "E_2") (pintype "passive"))
      (node (ref "T46") (pin "2") (pinfunction "E_2") (pintype "passive"))
      (node (ref "T47") (pin "2") (pinfunction "E_2") (pintype "passive"))
      (node (ref "T48") (pin "2") (pinfunction "E_2") (pintype "passive"))
      (node (ref "T49") (pin "2") (pinfunction "E_2") (pintype "passive"))
      (node (ref "T50") (pin "2") (pinfunction "E_2") (pintype "passive"))
      (node (ref "T51") (pin "2") (pinfunction "E_2") (pintype "passive"))
      (node (ref "T52") (pin "2") (pinfunction "E_2") (pintype "passive"))
      (node (ref "T53") (pin "2") (pinfunction "E_2") (pintype "passive"))
      (node (ref "T54") (pin "2") (pinfunction "E_2") (pintype "passive"))
      (node (ref "T55") (pin "2") (pinfunction "E_2") (pintype "passive"))
      (node (ref "T56") (pin "2") (pinfunction "E_2") (pintype "passive"))
      (node (ref "T57") (pin "2") (pinfunction "E_2") (pintype "passive"))
      (node (ref "T58") (pin "2") (pinfunction "E_2") (pintype "passive"))
      (node (ref "T59") (pin "2") (pinfunction "E_2") (pintype "passive"))
      (node (ref "T60") (pin "2") (pinfunction "E_2") (pintype "passive"))
      (node (ref "T61") (pin "2") (pinfunction "E_2") (pintype "passive"))
      (node (ref "T62") (pin "2") (pinfunction "E_2") (pintype "passive"))
      (node (ref "T63") (pin "2") (pinfunction "E_2") (pintype "passive"))
      (node (ref "T64") (pin "2") (pinfunction "E_2") (pintype "passive"))
      (node (ref "T65") (pin "2") (pinfunction "E_2") (pintype "passive"))
      (node (ref "T66") (pin "2") (pinfunction "E_2") (pintype "passive"))
      (node (ref "T67") (pin "2") (pinfunction "E_2") (pintype "passive"))
      (node (ref "T68") (pin "2") (pinfunction "E_2") (pintype "passive"))
      (node (ref "T69") (pin "2") (pinfunction "E_2") (pintype "passive"))
    )
    (net (code "197") (name "Net-(GL1-A)") (class "Default")
      (node (ref "GL1") (pin "1") (pinfunction "A_1") (pintype "passive"))
      (node (ref "R1") (pin "1") (pinfunction "1_1") (pintype "passive"))
    )
    (net (code "198") (name "Net-(GL1-A1)") (class "Default")
      (node (ref "GL1") (pin "2") (pinfunction "A1_2") (pintype "passive"))
      (node (ref "T1") (pin "3") (pinfunction "C_3") (pintype "passive"))
    )
    (net (code "199") (name "Net-(GL2-A)") (class "Default")
      (node (ref "GL2") (pin "1") (pinfunction "A_1") (pintype "passive"))
      (node (ref "R2") (pin "1") (pinfunction "1_1") (pintype "passive"))
    )
    (net (code "200") (name "Net-(GL2-A1)") (class "Default")
      (node (ref "GL2") (pin "2") (pinfunction "A1_2") (pintype "passive"))
      (node (ref "T2") (pin "3") (pinfunction "C_3") (pintype "passive"))
    )
    (net (code "201") (name "Net-(GL3-A)") (class "Default")
      (node (ref "GL3") (pin "1") (pinfunction "A_1") (pintype "passive"))
      (node (ref "R3") (pin "1") (pinfunction "1_1") (pintype "passive"))
    )
    (net (code "202") (name "Net-(GL3-A1)") (class "Default")
      (node (ref "GL3") (pin "2") (pinfunction "A1_2") (pintype "passive"))
      (node (ref "T3") (pin "3") (pinfunction "C_3") (pintype "passive"))
    )
    (net (code "203") (name "Net-(GL4-A)") (class "Default")
      (node (ref "GL4") (pin "1") (pinfunction "A_1") (pintype "passive"))
      (node (ref "R4") (pin "1") (pinfunction "1_1") (pintype "passive"))
    )
    (net (code "204") (name "Net-(GL4-A1)") (class "Default")
      (node (ref "GL4") (pin "2") (pinfunction "A1_2") (pintype "passive"))
      (node (ref "T4") (pin "3") (pinfunction "C_3") (pintype "passive"))
    )
    (net (code "205") (name "Net-(IC1A-QH*)") (class "Default")
      (node (ref "IC1") (pin "9") (pinfunction "QH*_9") (pintype "tri_state"))
      (node (ref "IC2") (pin "14") (pinfunction "SER_14") (pintype "input"))
    )
    (net (code "206") (name "Net-(IC2A-QH*)") (class "Default")
      (node (ref "IC2") (pin "9") (pinfunction "QH*_9") (pintype "tri_state"))
      (node (ref "IC3") (pin "14") (pinfunction "SER_14") (pintype "input"))
    )
    (net (code "207") (name "Net-(IC3A-QH*)") (class "Default")
      (node (ref "IC3") (pin "9") (pinfunction "QH*_9") (pintype "tri_state"))
      (node (ref "IC4") (pin "14") (pinfunction "SER_14") (pintype "input"))
    )
    (net (code "208") (name "Net-(IC4A-QH*)") (class "Default")
      (node (ref "IC4") (pin "9") (pinfunction "QH*_9") (pintype "tri_state"))
      (node (ref "IC5") (pin "14") (pinfunction "SER_14") (pintype "input"))
    )
    (net (code "209") (name "Net-(IC5A-QH*)") (class "Default")
      (node (ref "IC5") (pin "9") (pinfunction "QH*_9") (pintype "tri_state"))
      (node (ref "IC6") (pin "14") (pinfunction "SER_14") (pintype "input"))
    )
    (net (code "210") (name "Net-(IC6A-QH*)") (class "Default")
      (node (ref "IC6") (pin "9") (pinfunction "QH*_9") (pintype "tri_state"))
      (node (ref "IC7") (pin "14") (pinfunction "SER_14") (pintype "input"))
    )
    (net (code "211") (name "Net-(IC7A-QH*)") (class "Default")
      (node (ref "IC7") (pin "9") (pinfunction "QH*_9") (pintype "tri_state"))
      (node (ref "IC8") (pin "14") (pinfunction "SER_14") (pintype "input"))
    )
    (net (code "212") (name "Net-(N1-A-PadA1)") (class "Default")
      (node (ref "N1") (pin "A1") (pinfunction "A_A1") (pintype "bidirectional"))
      (node (ref "N1") (pin "A2") (pinfunction "A_A2") (pintype "bidirectional"))
      (node (ref "R10") (pin "1") (pinfunction "1_1") (pintype "passive"))
    )
    (net (code "213") (name "Net-(N1-PadPR)") (class "Default")
      (node (ref "N1") (pin "PR") (pinfunction "PR_PR") (pintype "bidirectional"))
      (node (ref "R11") (pin "2") (pinfunction "2_2") (pintype "passive"))
    )
    (net (code "214") (name "Net-(N2-A-PadA1)") (class "Default")
      (node (ref "N2") (pin "A1") (pinfunction "A_A1") (pintype "bidirectional"))
      (node (ref "N2") (pin "A2") (pinfunction "A_A2") (pintype "bidirectional"))
      (node (ref "R20") (pin "1") (pinfunction "1_1") (pintype "passive"))
    )
    (net (code "215") (name "Net-(N2-PadPR)") (class "Default")
      (node (ref "N2") (pin "PR") (pinfunction "PR_PR") (pintype "bidirectional"))
      (node (ref "R21") (pin "2") (pinfunction "2_2") (pintype "passive"))
    )
    (net (code "216") (name "Net-(N3-A-PadA1)") (class "Default")
      (node (ref "N3") (pin "A1") (pinfunction "A_A1") (pintype "bidirectional"))
      (node (ref "N3") (pin "A2") (pinfunction "A_A2") (pintype "bidirectional"))
      (node (ref "R30") (pin "1") (pinfunction "1_1") (pintype "passive"))
    )
    (net (code "217") (name "Net-(N3-PadPR)") (class "Default")
      (node (ref "N3") (pin "PR") (pinfunction "PR_PR") (pintype "bidirectional"))
      (node (ref "R31") (pin "2") (pinfunction "2_2") (pintype "passive"))
    )
    (net (code "218") (name "Net-(N4-A-PadA1)") (class "Default")
      (node (ref "N4") (pin "A1") (pinfunction "A_A1") (pintype "bidirectional"))
      (node (ref "N4") (pin "A2") (pinfunction "A_A2") (pintype "bidirectional"))
      (node (ref "R40") (pin "1") (pinfunction "1_1") (pintype "passive"))
    )
    (net (code "219") (name "Net-(N4-PadPR)") (class "Default")
      (node (ref "N4") (pin "PR") (pinfunction "PR_PR") (pintype "bidirectional"))
      (node (ref "R41") (pin "2") (pinfunction "2_2") (pintype "passive"))
    )
    (net (code "220") (name "Net-(N5-A-PadA1)") (class "Default")
      (node (ref "N5") (pin "A1") (pinfunction "A_A1") (pintype "bidirectional"))
      (node (ref "N5") (pin "A2") (pinfunction "A_A2") (pintype "bidirectional"))
      (node (ref "R50") (pin "1") (pinfunction "1_1") (pintype "passive"))
    )
    (net (code "221") (name "Net-(N5-PadPR)") (class "Default")
      (node (ref "N5") (pin "PR") (pinfunction "PR_PR") (pintype "bidirectional"))
      (node (ref "R51") (pin "2") (pinfunction "2_2") (pintype "passive"))
    )
    (net (code "222") (name "Net-(N6-A-PadA1)") (class "Default")
      (node (ref "N6") (pin "A1") (pinfunction "A_A1") (pintype "bidirectional"))
      (node (ref "N6") (pin "A2") (pinfunction "A_A2") (pintype "bidirectional"))
      (node (ref "R60") (pin "1") (pinfunction "1_1") (pintype "passive"))
    )
    (net (code "223") (name "Net-(N6-PadPR)") (class "Default")
      (node (ref "N6") (pin "PR") (pinfunction "PR_PR") (pintype "bidirectional"))
      (node (ref "R61") (pin "2") (pinfunction "2_2") (pintype "passive"))
    )
    (net (code "224") (name "VDD") (class "Default")
      (node (ref "JP2") (pin "1") (pinfunction "1_1") (pintype "passive"))
      (node (ref "R1") (pin "2") (pinfunction "2_2") (pintype "passive"))
      (node (ref "R10") (pin "2") (pinfunction "2_2") (pintype "passive"))
      (node (ref "R2") (pin "2") (pinfunction "2_2") (pintype "passive"))
      (node (ref "R20") (pin "2") (pinfunction "2_2") (pintype "passive"))
      (node (ref "R3") (pin "2") (pinfunction "2_2") (pintype "passive"))
      (node (ref "R30") (pin "2") (pinfunction "2_2") (pintype "passive"))
      (node (ref "R4") (pin "2") (pinfunction "2_2") (pintype "passive"))
      (node (ref "R40") (pin "2") (pinfunction "2_2") (pintype "passive"))
      (node (ref "R50") (pin "2") (pinfunction "2_2") (pintype "passive"))
      (node (ref "R60") (pin "2") (pinfunction "2_2") (pintype "passive"))
    )
    (net (code "225") (name "unconnected-(IC8A-QH*-Pad9)") (class "Default")
      (node (ref "IC8") (pin "9") (pinfunction "QH*_9") (pintype "tri_state"))
    )
    (net (code "226") (name "unconnected-(N2-DP-PadKDP)") (class "Default")
      (node (ref "N2") (pin "KDP") (pinfunction "DP_KDP") (pintype "bidirectional"))
    )
    (net (code "227") (name "unconnected-(N3-DP-PadKDP)") (class "Default")
      (node (ref "N3") (pin "KDP") (pinfunction "DP_KDP") (pintype "bidirectional"))
    )
    (net (code "228") (name "unconnected-(N4-DP-PadKDP)") (class "Default")
      (node (ref "N4") (pin "KDP") (pinfunction "DP_KDP") (pintype "bidirectional"))
    )
    (net (code "229") (name "unconnected-(N5-DP-PadKDP)") (class "Default")
      (node (ref "N5") (pin "KDP") (pinfunction "DP_KDP") (pintype "bidirectional"))
    )
    (net (code "230") (name "unconnected-(N6-DP-PadKDP)") (class "Default")
      (node (ref "N6") (pin "KDP") (pinfunction "DP_KDP") (pintype "bidirectional"))
    )
  )
)
